# Nucleo.net
KiCad netlist of a schematic drawn in Altium Designer
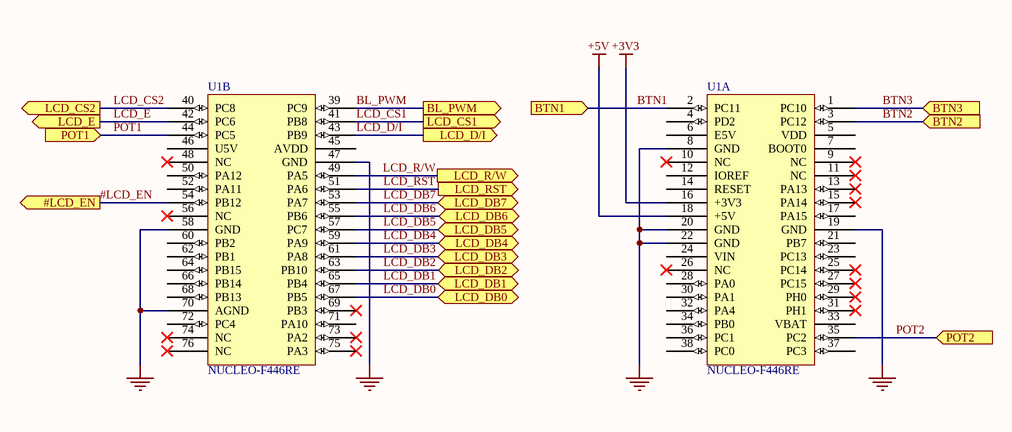
[diagram p0: Nucleo.SchDoc]

(export (version "E")
  (design (tool "Eeschema 10.0.6"))
  (components
    (comp (ref "U1")
      (value "NUCLEO-F446RE")
      (footprint "FP_NUCLEO-64_2x20")
      (description "Development kit")
      (libsource (lib "hallglib") (part "NUCLEO-F446RE"))
    )
  )
  (nets
    (net (code "1") (name "+3V3") (class "Default")
      (node (ref "U1") (pin "16") (pinfunction "+3V3_16") (pintype "power_in"))
    )
    (net (code "2") (name "+5V") (class "Default")
      (node (ref "U1") (pin "18") (pinfunction "+5V_18") (pintype "power_in"))
    )
    (net (code "3") (name "/#LCD_EN") (class "Default")
      (node (ref "U1") (pin "54") (pinfunction "PB12_54") (pintype "bidirectional"))
    )
    (net (code "4") (name "/BL_PWM") (class "Default")
      (node (ref "U1") (pin "39") (pinfunction "PC9_39") (pintype "bidirectional"))
    )
    (net (code "5") (name "/BTN1") (class "Default")
      (node (ref "U1") (pin "2") (pinfunction "PC11_2") (pintype "bidirectional"))
    )
    (net (code "6") (name "/BTN2") (class "Default")
      (node (ref "U1") (pin "3") (pinfunction "PC12_3") (pintype "bidirectional"))
    )
    (net (code "7") (name "/BTN3") (class "Default")
      (node (ref "U1") (pin "1") (pinfunction "PC10_1") (pintype "bidirectional"))
    )
    (net (code "8") (name "/LCD_CS1") (class "Default")
      (node (ref "U1") (pin "41") (pinfunction "PB8_41") (pintype "bidirectional"))
    )
    (net (code "9") (name "/LCD_CS2") (class "Default")
      (node (ref "U1") (pin "40") (pinfunction "PC8_40") (pintype "bidirectional"))
    )
    (net (code "10") (name "/LCD_DB0") (class "Default")
      (node (ref "U1") (pin "67") (pinfunction "PB5_67") (pintype "bidirectional"))
    )
    (net (code "11") (name "/LCD_DB1") (class "Default")
      (node (ref "U1") (pin "65") (pinfunction "PB4_65") (pintype "bidirectional"))
    )
    (net (code "12") (name "/LCD_DB2") (class "Default")
      (node (ref "U1") (pin "63") (pinfunction "PB10_63") (pintype "bidirectional"))
    )
    (net (code "13") (name "/LCD_DB3") (class "Default")
      (node (ref "U1") (pin "61") (pinfunction "PA8_61") (pintype "bidirectional"))
    )
    (net (code "14") (name "/LCD_DB4") (class "Default")
      (node (ref "U1") (pin "59") (pinfunction "PA9_59") (pintype "bidirectional"))
    )
    (net (code "15") (name "/LCD_DB5") (class "Default")
      (node (ref "U1") (pin "57") (pinfunction "PC7_57") (pintype "bidirectional"))
    )
    (net (code "16") (name "/LCD_DB6") (class "Default")
      (node (ref "U1") (pin "55") (pinfunction "PB6_55") (pintype "bidirectional"))
    )
    (net (code "17") (name "/LCD_DB7") (class "Default")
      (node (ref "U1") (pin "53") (pinfunction "PA7_53") (pintype "bidirectional"))
    )
    (net (code "18") (name "/LCD_D{slash}I") (class "Default")
      (node (ref "U1") (pin "43") (pinfunction "PB9_43") (pintype "bidirectional"))
    )
    (net (code "19") (name "/LCD_E") (class "Default")
      (node (ref "U1") (pin "42") (pinfunction "PC6_42") (pintype "bidirectional"))
    )
    (net (code "20") (name "/LCD_RST") (class "Default")
      (node (ref "U1") (pin "51") (pinfunction "PA6_51") (pintype "bidirectional"))
    )
    (net (code "21") (name "/LCD_R{slash}W") (class "Default")
      (node (ref "U1") (pin "49") (pinfunction "PA5_49") (pintype "bidirectional"))
    )
    (net (code "22") (name "/POT1") (class "Default")
      (node (ref "U1") (pin "44") (pinfunction "PC5_44") (pintype "bidirectional"))
    )
    (net (code "23") (name "/POT2") (class "Default")
      (node (ref "U1") (pin "35") (pinfunction "PC2_35") (pintype "bidirectional"))
    )
    (net (code "24") (name "GND") (class "Default")
      (node (ref "U1") (pin "19") (pinfunction "GND_19") (pintype "passive"))
      (node (ref "U1") (pin "20") (pinfunction "GND_20") (pintype "passive"))
      (node (ref "U1") (pin "22") (pinfunction "GND_22") (pintype "passive"))
      (node (ref "U1") (pin "47") (pinfunction "GND_47") (pintype "passive"))
      (node (ref "U1") (pin "58") (pinfunction "GND_58") (pintype "passive"))
      (node (ref "U1") (pin "70") (pinfunction "AGND_70") (pintype "passive"))
      (node (ref "U1") (pin "8") (pinfunction "GND_8") (pintype "passive"))
    )
    (net (code "25") (name "unconnected-(U1A-BOOT0-Pad7)") (class "Default")
      (node (ref "U1") (pin "7") (pinfunction "BOOT0_7") (pintype "passive"))
    )
    (net (code "26") (name "unconnected-(U1A-E5V-Pad6)") (class "Default")
      (node (ref "U1") (pin "6") (pinfunction "E5V_6") (pintype "power_in"))
    )
    (net (code "27") (name "unconnected-(U1A-IOREF-Pad12)") (class "Default")
      (node (ref "U1") (pin "12") (pinfunction "IOREF_12") (pintype "passive"))
    )
    (net (code "28") (name "unconnected-(U1A-NC-Pad9)") (class "Default")
      (node (ref "U1") (pin "9") (pinfunction "NC_9") (pintype "passive+no_connect"))
    )
    (net (code "29") (name "unconnected-(U1A-NC-Pad10)") (class "Default")
      (node (ref "U1") (pin "10") (pinfunction "NC_10") (pintype "passive+no_connect"))
    )
    (net (code "30") (name "unconnected-(U1A-NC-Pad11)") (class "Default")
      (node (ref "U1") (pin "11") (pinfunction "NC_11") (pintype "passive+no_connect"))
    )
    (net (code "31") (name "unconnected-(U1A-NC-Pad26)") (class "Default")
      (node (ref "U1") (pin "26") (pinfunction "NC_26") (pintype "passive+no_connect"))
    )
    (net (code "32") (name "unconnected-(U1A-PA0-Pad28)") (class "Default")
      (node (ref "U1") (pin "28") (pinfunction "PA0_28") (pintype "bidirectional"))
    )
    (net (code "33") (name "unconnected-(U1A-PA1-Pad30)") (class "Default")
      (node (ref "U1") (pin "30") (pinfunction "PA1_30") (pintype "bidirectional"))
    )
    (net (code "34") (name "unconnected-(U1A-PA4-Pad32)") (class "Default")
      (node (ref "U1") (pin "32") (pinfunction "PA4_32") (pintype "bidirectional"))
    )
    (net (code "35") (name "unconnected-(U1A-PA13-Pad13)") (class "Default")
      (node (ref "U1") (pin "13") (pinfunction "PA13_13") (pintype "bidirectional+no_connect"))
    )
    (net (code "36") (name "unconnected-(U1A-PA14-Pad15)") (class "Default")
      (node (ref "U1") (pin "15") (pinfunction "PA14_15") (pintype "bidirectional+no_connect"))
    )
    (net (code "37") (name "unconnected-(U1A-PA15-Pad17)") (class "Default")
      (node (ref "U1") (pin "17") (pinfunction "PA15_17") (pintype "bidirectional"))
    )
    (net (code "38") (name "unconnected-(U1A-PB0-Pad34)") (class "Default")
      (node (ref "U1") (pin "34") (pinfunction "PB0_34") (pintype "bidirectional"))
    )
    (net (code "39") (name "unconnected-(U1A-PB7-Pad21)") (class "Default")
      (node (ref "U1") (pin "21") (pinfunction "PB7_21") (pintype "bidirectional"))
    )
    (net (code "40") (name "unconnected-(U1A-PC0-Pad38)") (class "Default")
      (node (ref "U1") (pin "38") (pinfunction "PC0_38") (pintype "bidirectional"))
    )
    (net (code "41") (name "unconnected-(U1A-PC1-Pad36)") (class "Default")
      (node (ref "U1") (pin "36") (pinfunction "PC1_36") (pintype "bidirectional"))
    )
    (net (code "42") (name "unconnected-(U1A-PC3-Pad37)") (class "Default")
      (node (ref "U1") (pin "37") (pinfunction "PC3_37") (pintype "bidirectional"))
    )
    (net (code "43") (name "unconnected-(U1A-PC13-Pad23)") (class "Default")
      (node (ref "U1") (pin "23") (pinfunction "PC13_23") (pintype "bidirectional"))
    )
    (net (code "44") (name "unconnected-(U1A-PC14-Pad25)") (class "Default")
      (node (ref "U1") (pin "25") (pinfunction "PC14_25") (pintype "bidirectional+no_connect"))
    )
    (net (code "45") (name "unconnected-(U1A-PC15-Pad27)") (class "Default")
      (node (ref "U1") (pin "27") (pinfunction "PC15_27") (pintype "bidirectional+no_connect"))
    )
    (net (code "46") (name "unconnected-(U1A-PD2-Pad4)") (class "Default")
      (node (ref "U1") (pin "4") (pinfunction "PD2_4") (pintype "bidirectional"))
    )
    (net (code "47") (name "unconnected-(U1A-PH0-Pad29)") (class "Default")
      (node (ref "U1") (pin "29") (pinfunction "PH0_29") (pintype "bidirectional+no_connect"))
    )
    (net (code "48") (name "unconnected-(U1A-PH1-Pad31)") (class "Default")
      (node (ref "U1") (pin "31") (pinfunction "PH1_31") (pintype "bidirectional+no_connect"))
    )
    (net (code "49") (name "unconnected-(U1A-RESET-Pad14)") (class "Default")
      (node (ref "U1") (pin "14") (pinfunction "RESET_14") (pintype "passive"))
    )
    (net (code "50") (name "unconnected-(U1A-VBAT-Pad33)") (class "Default")
      (node (ref "U1") (pin "33") (pinfunction "VBAT_33") (pintype "power_in"))
    )
    (net (code "51") (name "unconnected-(U1A-VDD-Pad5)") (class "Default")
      (node (ref "U1") (pin "5") (pinfunction "VDD_5") (pintype "power_in"))
    )
    (net (code "52") (name "unconnected-(U1A-VIN-Pad24)") (class "Default")
      (node (ref "U1") (pin "24") (pinfunction "VIN_24") (pintype "power_in"))
    )
    (net (code "53") (name "unconnected-(U1B-AVDD-Pad45)") (class "Default")
      (node (ref "U1") (pin "45") (pinfunction "AVDD_45") (pintype "power_in"))
    )
    (net (code "54") (name "unconnected-(U1B-NC-Pad48)") (class "Default")
      (node (ref "U1") (pin "48") (pinfunction "NC_48") (pintype "passive+no_connect"))
    )
    (net (code "55") (name "unconnected-(U1B-NC-Pad56)") (class "Default")
      (node (ref "U1") (pin "56") (pinfunction "NC_56") (pintype "passive+no_connect"))
    )
    (net (code "56") (name "unconnected-(U1B-NC-Pad74)") (class "Default")
      (node (ref "U1") (pin "74") (pinfunction "NC_74") (pintype "passive+no_connect"))
    )
    (net (code "57") (name "unconnected-(U1B-NC-Pad76)") (class "Default")
      (node (ref "U1") (pin "76") (pinfunction "NC_76") (pintype "passive+no_connect"))
    )
    (net (code "58") (name "unconnected-(U1B-PA2-Pad73)") (class "Default")
      (node (ref "U1") (pin "73") (pinfunction "PA2_73") (pintype "bidirectional+no_connect"))
    )
    (net (code "59") (name "unconnected-(U1B-PA3-Pad75)") (class "Default")
      (node (ref "U1") (pin "75") (pinfunction "PA3_75") (pintype "bidirectional+no_connect"))
    )
    (net (code "60") (name "unconnected-(U1B-PA10-Pad71)") (class "Default")
      (node (ref "U1") (pin "71") (pinfunction "PA10_71") (pintype "bidirectional"))
    )
    (net (code "61") (name "unconnected-(U1B-PA11-Pad52)") (class "Default")
      (node (ref "U1") (pin "52") (pinfunction "PA11_52") (pintype "bidirectional"))
    )
    (net (code "62") (name "unconnected-(U1B-PA12-Pad50)") (class "Default")
      (node (ref "U1") (pin "50") (pinfunction "PA12_50") (pintype "bidirectional"))
    )
    (net (code "63") (name "unconnected-(U1B-PB1-Pad62)") (class "Default")
      (node (ref "U1") (pin "62") (pinfunction "PB1_62") (pintype "bidirectional"))
    )
    (net (code "64") (name "unconnected-(U1B-PB2-Pad60)") (class "Default")
      (node (ref "U1") (pin "60") (pinfunction "PB2_60") (pintype "bidirectional"))
    )
    (net (code "65") (name "unconnected-(U1B-PB3-Pad69)") (class "Default")
      (node (ref "U1") (pin "69") (pinfunction "PB3_69") (pintype "bidirectional+no_connect"))
    )
    (net (code "66") (name "unconnected-(U1B-PB13-Pad68)") (class "Default")
      (node (ref "U1") (pin "68") (pinfunction "PB13_68") (pintype "bidirectional"))
    )
    (net (code "67") (name "unconnected-(U1B-PB14-Pad66)") (class "Default")
      (node (ref "U1") (pin "66") (pinfunction "PB14_66") (pintype "bidirectional"))
    )
    (net (code "68") (name "unconnected-(U1B-PB15-Pad64)") (class "Default")
      (node (ref "U1") (pin "64") (pinfunction "PB15_64") (pintype "bidirectional"))
    )
    (net (code "69") (name "unconnected-(U1B-PC4-Pad72)") (class "Default")
      (node (ref "U1") (pin "72") (pinfunction "PC4_72") (pintype "bidirectional"))
    )
    (net (code "70") (name "unconnected-(U1B-U5V-Pad46)") (class "Default")
      (node (ref "U1") (pin "46") (pinfunction "U5V_46") (pintype "power_in"))
    )
  )
)
